# SCHEMATIC.net
KiCad netlist of a schematic drawn in EAGLE
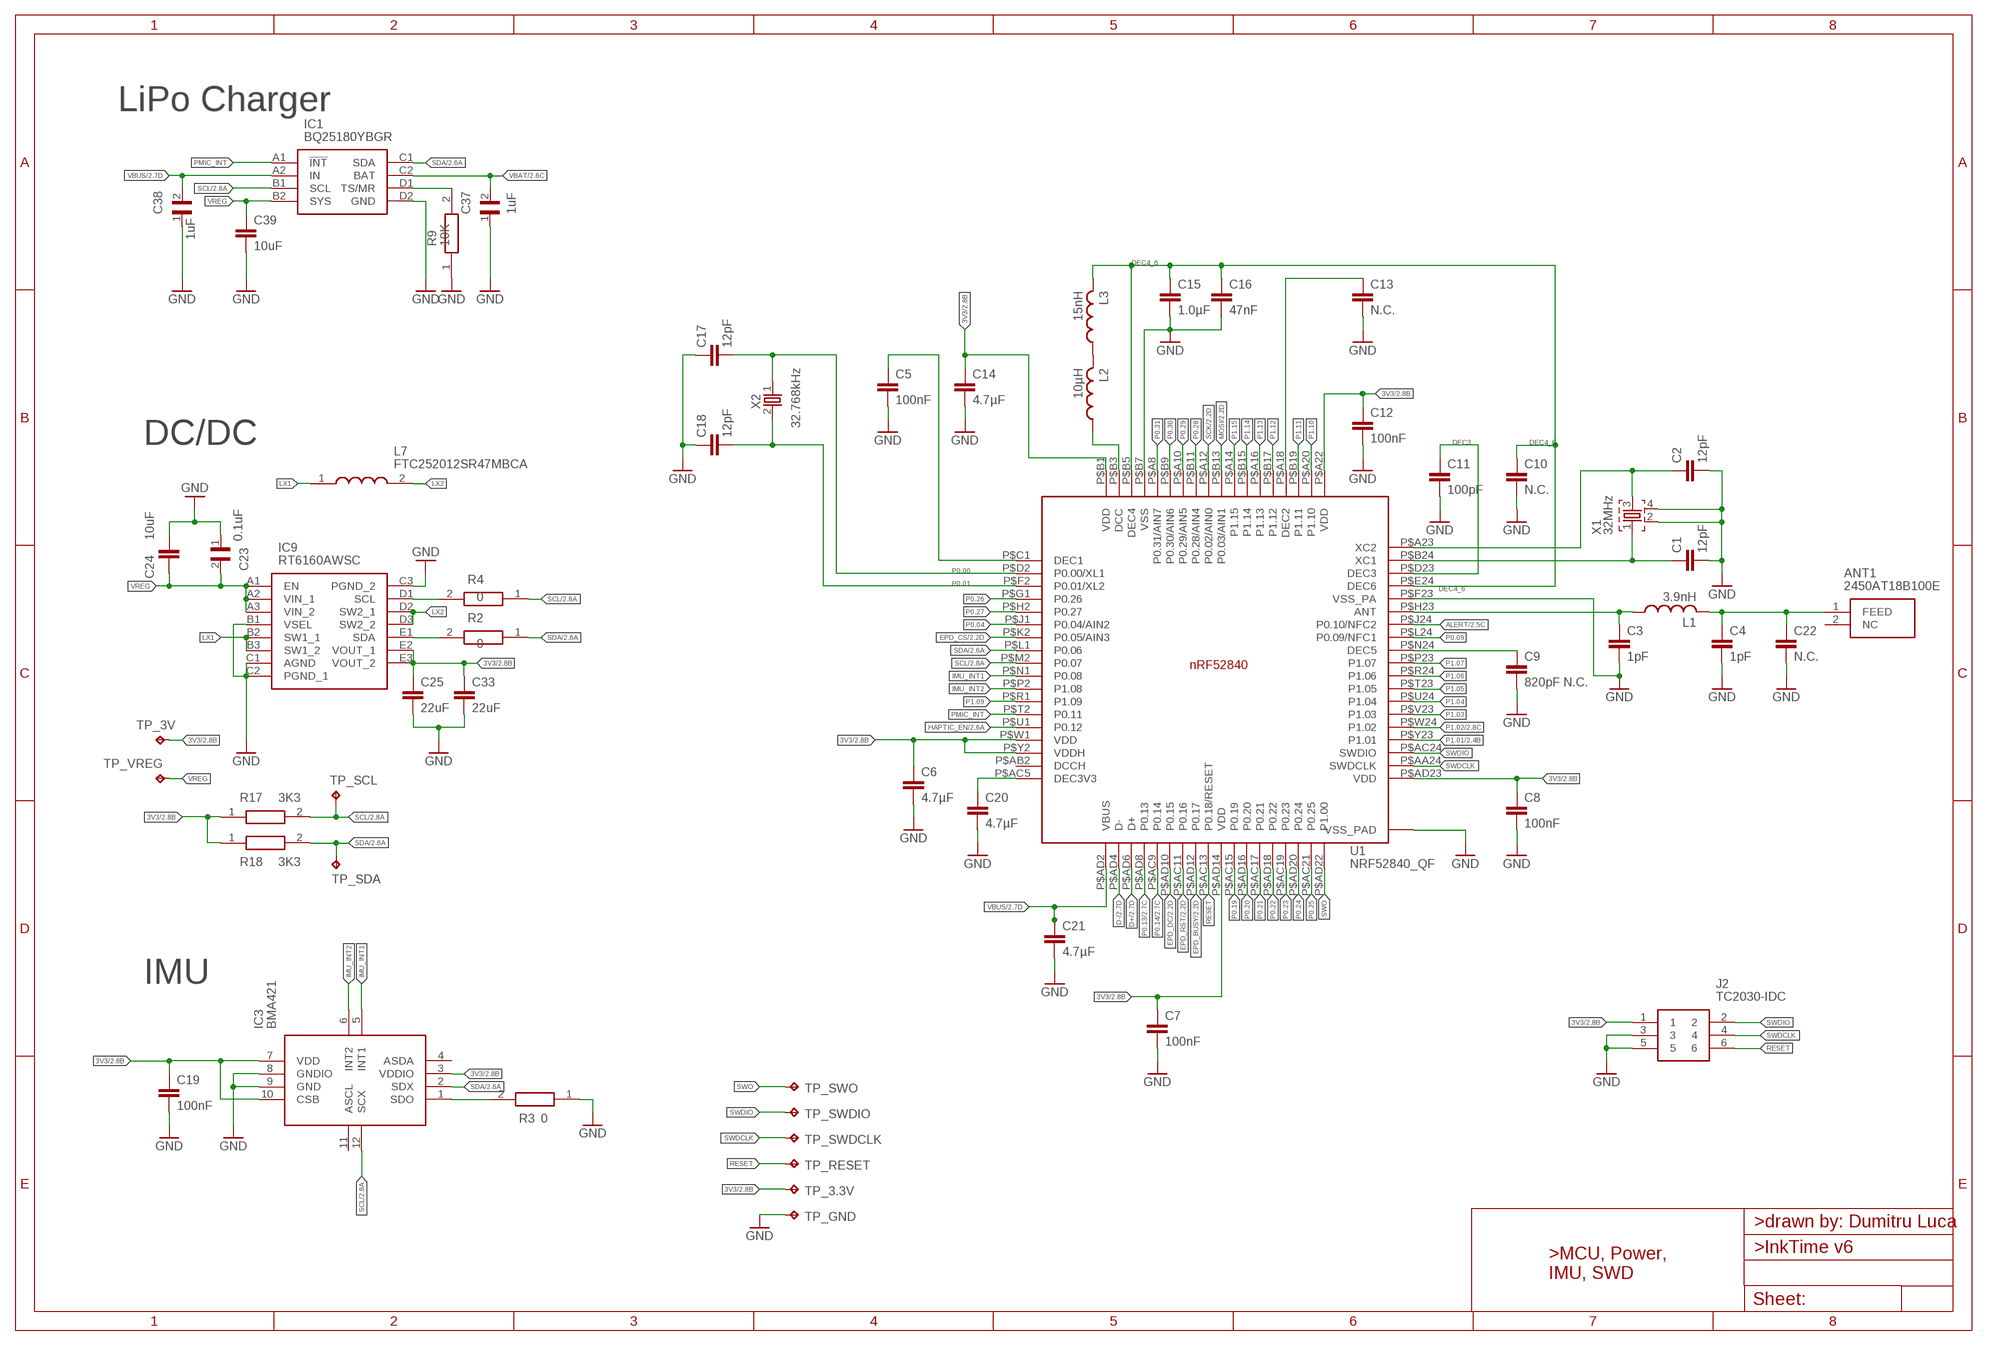
[diagram p0: schematic, sheet 1]
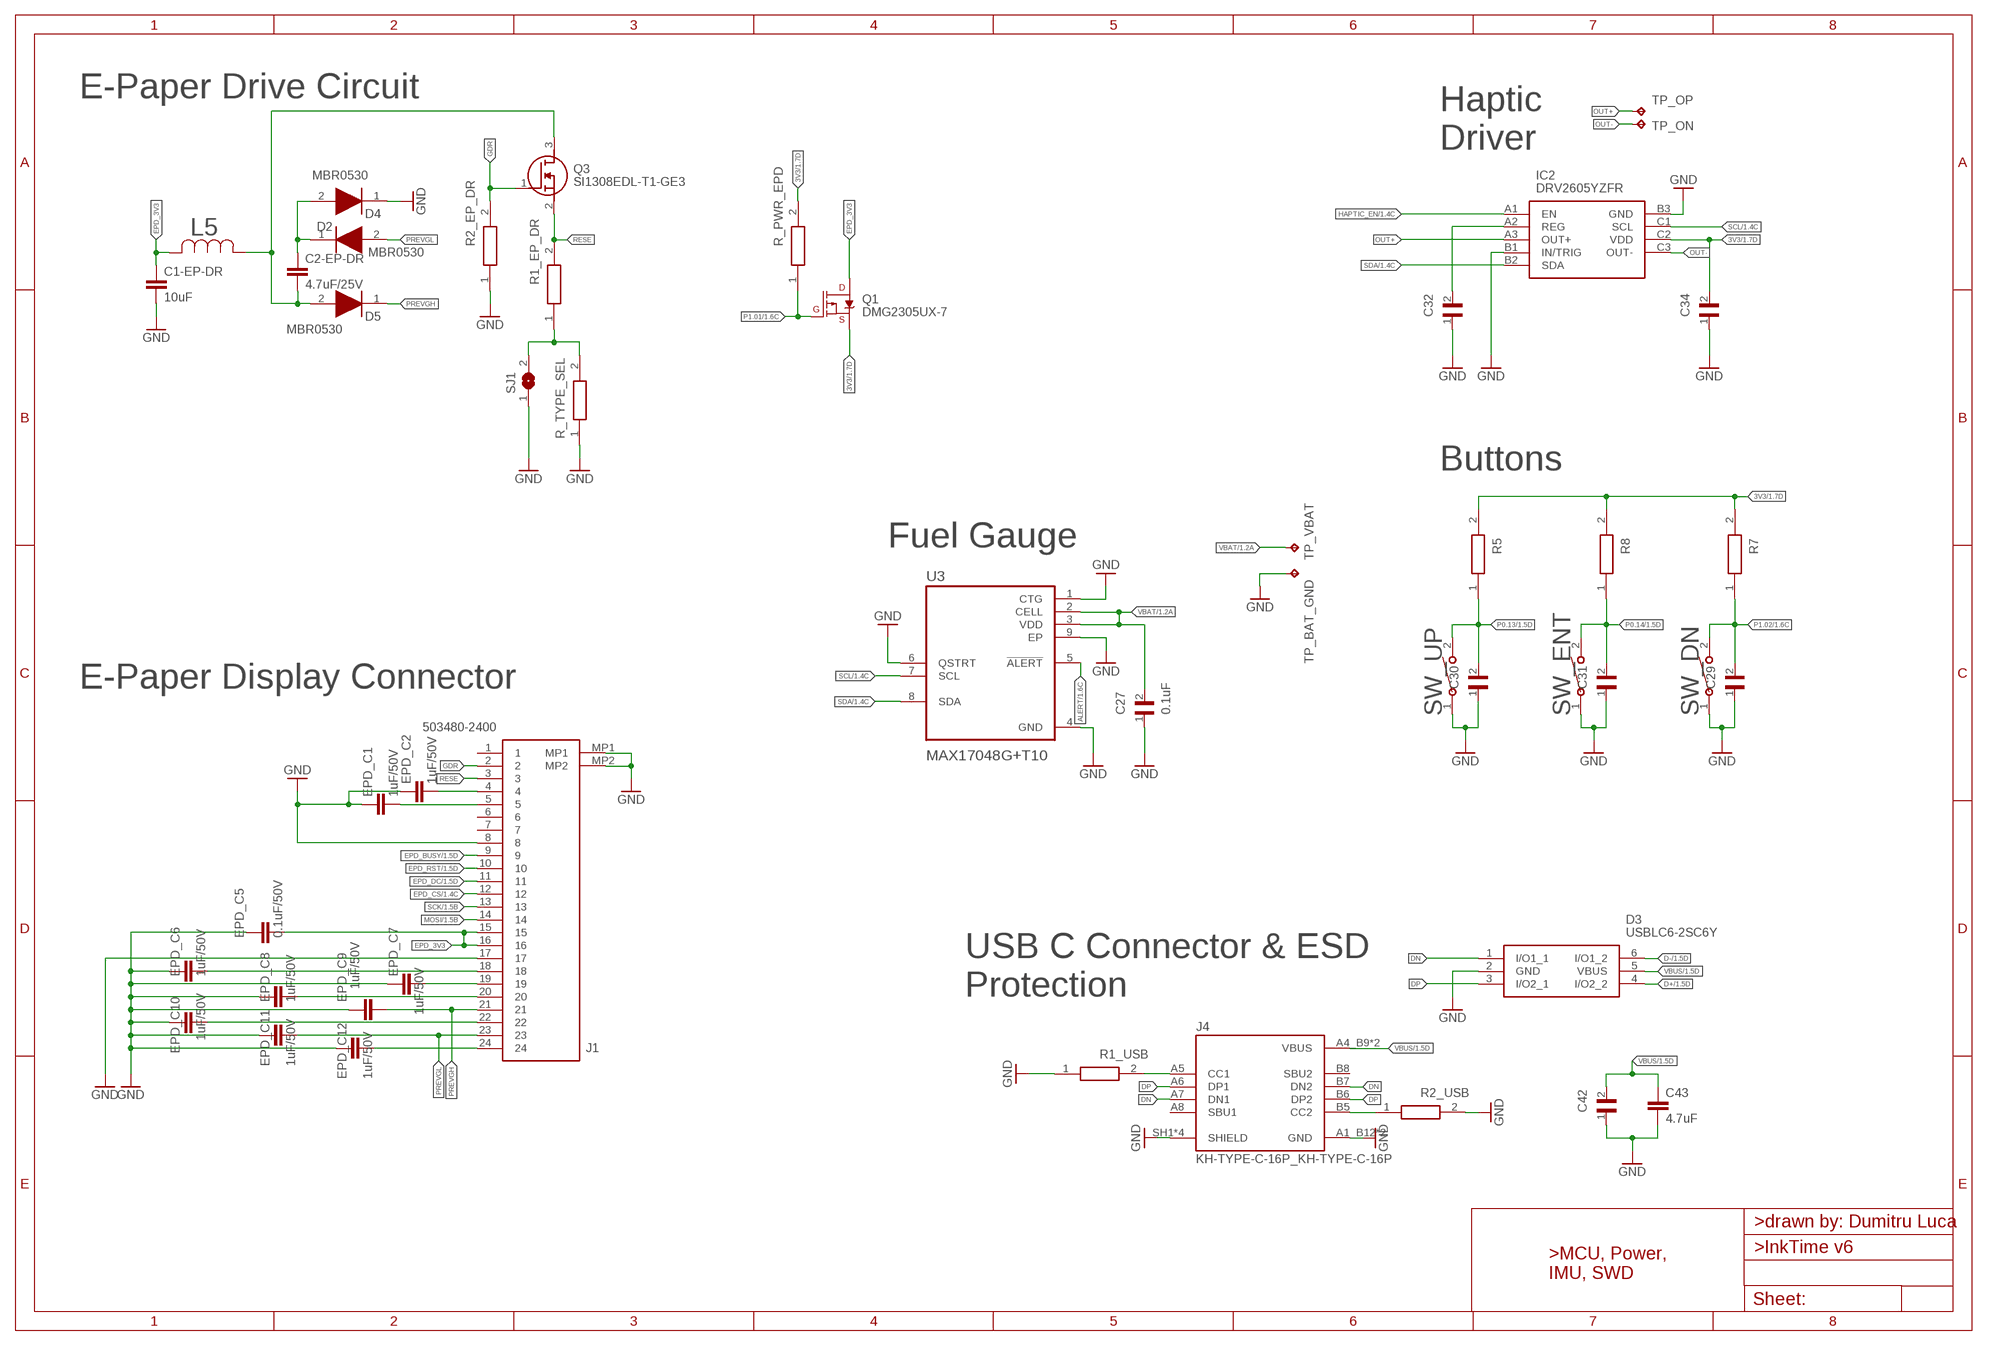
[diagram p1: schematic, sheet 2]

(export (version "E")
  (design (tool "Eeschema 10.0.6"))
  (components
    (comp (ref "ANT1")
      (value "2450AT18B100E")
      (footprint "eagle-import:2450AT18B100E_ANTC3216X140N")
      (fields (field (name "MOUSER_PART_NUMBER") "609-2450AT18B100E"))
      (libsource (lib "eagle-import") (part "2450AT18B100E_2450AT18B100E"))
    )
    (comp (ref "C1")
      (value "12pF")
      (footprint "eagle-import:NORDIC_NRF_3_RESC0201_L")
      (libsource (lib "eagle-import") (part "NORDIC_NRF_3_CAPACITOR_0201_L"))
    )
    (comp (ref "C2")
      (value "12pF")
      (footprint "eagle-import:NORDIC_NRF_3_RESC0201_L")
      (libsource (lib "eagle-import") (part "NORDIC_NRF_3_CAPACITOR_0201_L"))
    )
    (comp (ref "C3")
      (value "1pF")
      (footprint "eagle-import:NORDIC_NRF_3_RESC0201_L")
      (libsource (lib "eagle-import") (part "NORDIC_NRF_3_CAPACITOR_0201_L"))
    )
    (comp (ref "C4")
      (value "1pF")
      (footprint "eagle-import:NORDIC_NRF_3_RESC0201_L")
      (libsource (lib "eagle-import") (part "NORDIC_NRF_3_CAPACITOR_0201_L"))
    )
    (comp (ref "C5")
      (value "100nF")
      (footprint "eagle-import:NORDIC_NRF_3_RESC0201_L")
      (libsource (lib "eagle-import") (part "NORDIC_NRF_3_CAPACITOR_0201_L"))
    )
    (comp (ref "C6")
      (value "4.7µF")
      (footprint "eagle-import:NORDIC_NRF_3_RESC0201_L")
      (libsource (lib "eagle-import") (part "NORDIC_NRF_3_CAPACITOR_0201_L"))
    )
    (comp (ref "C7")
      (value "100nF")
      (footprint "eagle-import:NORDIC_NRF_3_RESC0201_L")
      (libsource (lib "eagle-import") (part "NORDIC_NRF_3_CAPACITOR_0201_L"))
    )
    (comp (ref "C8")
      (value "100nF")
      (footprint "eagle-import:NORDIC_NRF_3_RESC0201_L")
      (libsource (lib "eagle-import") (part "NORDIC_NRF_3_CAPACITOR_0201_L"))
    )
    (comp (ref "C9")
      (value "820pF N.C.")
      (footprint "eagle-import:NORDIC_NRF_3_RESC0201_L")
      (libsource (lib "eagle-import") (part "NORDIC_NRF_3_CAPACITOR_0201_L"))
    )
    (comp (ref "C10")
      (value "N.C.")
      (footprint "eagle-import:NORDIC_NRF_3_RESC0201_L")
      (libsource (lib "eagle-import") (part "NORDIC_NRF_3_CAPACITOR_0201_L"))
    )
    (comp (ref "C11")
      (value "100pF")
      (footprint "eagle-import:NORDIC_NRF_3_RESC0201_L")
      (libsource (lib "eagle-import") (part "NORDIC_NRF_3_CAPACITOR_0201_L"))
    )
    (comp (ref "C12")
      (value "100nF")
      (footprint "eagle-import:NORDIC_NRF_3_RESC0201_L")
      (libsource (lib "eagle-import") (part "NORDIC_NRF_3_CAPACITOR_0201_L"))
    )
    (comp (ref "C13")
      (value "N.C.")
      (footprint "eagle-import:NORDIC_NRF_3_RESC0201_L")
      (libsource (lib "eagle-import") (part "NORDIC_NRF_3_CAPACITOR_0201_L"))
    )
    (comp (ref "C14")
      (value "4.7µF")
      (footprint "eagle-import:NORDIC_NRF_3_RESC0201_L")
      (libsource (lib "eagle-import") (part "NORDIC_NRF_3_CAPACITOR_0201_L"))
    )
    (comp (ref "C15")
      (value "1.0µF")
      (footprint "eagle-import:NORDIC_NRF_3_RESC0201_L")
      (libsource (lib "eagle-import") (part "NORDIC_NRF_3_CAPACITOR_0201_L"))
    )
    (comp (ref "C16")
      (value "47nF")
      (footprint "eagle-import:NORDIC_NRF_3_RESC0201_L")
      (libsource (lib "eagle-import") (part "NORDIC_NRF_3_CAPACITOR_0201_L"))
    )
    (comp (ref "C17")
      (value "12pF")
      (footprint "eagle-import:NORDIC_NRF_3_RESC0201_L")
      (libsource (lib "eagle-import") (part "NORDIC_NRF_3_CAPACITOR_0201_L"))
    )
    (comp (ref "C18")
      (value "12pF")
      (footprint "eagle-import:NORDIC_NRF_3_RESC0201_L")
      (libsource (lib "eagle-import") (part "NORDIC_NRF_3_CAPACITOR_0201_L"))
    )
    (comp (ref "C19")
      (value "100nF")
      (footprint "eagle-import:NORDIC_NRF_3_RESC0201_L")
      (libsource (lib "eagle-import") (part "NORDIC_NRF_3_CAPACITOR_0201_L"))
    )
    (comp (ref "C20")
      (value "4.7µF")
      (footprint "eagle-import:NORDIC_NRF_3_RESC0201_L")
      (libsource (lib "eagle-import") (part "NORDIC_NRF_3_CAPACITOR_0201_L"))
    )
    (comp (ref "C21")
      (value "4.7µF")
      (footprint "eagle-import:NORDIC_NRF_3_RESC0201_L")
      (libsource (lib "eagle-import") (part "NORDIC_NRF_3_CAPACITOR_0201_L"))
    )
    (comp (ref "C22")
      (value "N.C.")
      (footprint "eagle-import:NORDIC_NRF_3_RESC0201_L")
      (libsource (lib "eagle-import") (part "NORDIC_NRF_3_CAPACITOR_0201_L"))
    )
    (comp (ref "C23")
      (value "0.1uF")
      (footprint "eagle-import:GRM011R60J152KE01L_1_0201")
      (libsource (lib "eagle-import") (part "GRM011R60J152KE01L_1_GRM011R60J152KE01L"))
    )
    (comp (ref "C24")
      (value "10uF")
      (footprint "eagle-import:NORDIC_NRF_3_RESC0402_L")
      (libsource (lib "eagle-import") (part "NORDIC_NRF_3_CAPACITOR_0402_L"))
    )
    (comp (ref "C25")
      (value "22uF")
      (footprint "eagle-import:NORDIC_NRF_3_RESC0402_L")
      (libsource (lib "eagle-import") (part "NORDIC_NRF_3_CAPACITOR_0402_L"))
    )
    (comp (ref "C33")
      (value "22uF")
      (footprint "eagle-import:NORDIC_NRF_3_RESC0402_L")
      (libsource (lib "eagle-import") (part "NORDIC_NRF_3_CAPACITOR_0402_L"))
    )
    (comp (ref "C37")
      (value "1uF")
      (footprint "eagle-import:GRM011R60J152KE01L_1_0201")
      (libsource (lib "eagle-import") (part "GRM011R60J152KE01L_1_GRM011R60J152KE01L"))
    )
    (comp (ref "C38")
      (value "1uF")
      (footprint "eagle-import:GRM011R60J152KE01L_1_0201")
      (libsource (lib "eagle-import") (part "GRM011R60J152KE01L_1_GRM011R60J152KE01L"))
    )
    (comp (ref "C39")
      (value "10uF")
      (footprint "eagle-import:NORDIC_NRF_3_RESC0402_L")
      (libsource (lib "eagle-import") (part "NORDIC_NRF_3_CAPACITOR_0402_L"))
    )
    (comp (ref "IC1")
      (value "BQ25180YBGR")
      (footprint "eagle-import:BQ25180YBGR_BGA8C40P2X4_100X155X50")
      (fields (field (name "MOUSER_PART_NUMBER") "595-BQ25180YBGR"))
      (libsource (lib "eagle-import") (part "BQ25180YBGR_BQ25180YBGR"))
    )
    (comp (ref "IC3")
      (value "BMA421")
      (footprint "eagle-import:BMA423_BMA423")
      (fields (field (name "ARROW_PART_NUMBER") "BMA423") (field (name "MOUSER_PART_NUMBER") "262-BMA423"))
      (libsource (lib "eagle-import") (part "BMA423_BMA423"))
    )
    (comp (ref "IC9")
      (value "RT6160AWSC")
      (footprint "eagle-import:RT6160AWSC_BGA15C40P3X5_140X230X60")
      (fields (field (name "MOUSER_PART_NUMBER") "835-RT6160AWSC"))
      (libsource (lib "eagle-import") (part "RT6160AWSC_RT6160AWSC"))
    )
    (comp (ref "J2")
      (value "TC2030-IDC")
      (footprint "eagle-import:TC2030-IDC_TC2030IDC")
      (libsource (lib "eagle-import") (part "TC2030-IDC_TC2030-IDC"))
    )
    (comp (ref "L1")
      (value "3.9nH")
      (footprint "eagle-import:NORDIC_NRF_2_RESC0402_L")
      (libsource (lib "eagle-import") (part "NORDIC_NRF_2_INDUCTOR_0402_L"))
    )
    (comp (ref "L2")
      (value "10µH")
      (footprint "eagle-import:NORDIC_NRF_2_RESC0402_L")
      (libsource (lib "eagle-import") (part "NORDIC_NRF_2_INDUCTOR_0402_L"))
    )
    (comp (ref "L3")
      (value "15nH")
      (footprint "eagle-import:NORDIC_NRF_2_RESC0402_L")
      (libsource (lib "eagle-import") (part "NORDIC_NRF_2_INDUCTOR_0402_L"))
    )
    (comp (ref "L7")
      (value "FTC252012SR47MBCA")
      (footprint "eagle-import:MLP2016SR47MT0S1_INDC2016X100N")
      (libsource (lib "eagle-import") (part "MLP2016SR47MT0S1_FTC252012SR47MBCA"))
    )
    (comp (ref "R2")
      (value "0")
      (footprint "eagle-import:CPF0201D7K68C1_0201")
      (libsource (lib "eagle-import") (part "CPF0201D7K68C1_CPF0201D7K68C1"))
    )
    (comp (ref "R3")
      (value "0")
      (footprint "eagle-import:CPF0201D7K68C1_0201")
      (libsource (lib "eagle-import") (part "CPF0201D7K68C1_CPF0201D7K68C1"))
    )
    (comp (ref "R4")
      (value "0")
      (footprint "eagle-import:CPF0201D7K68C1_0201")
      (libsource (lib "eagle-import") (part "CPF0201D7K68C1_CPF0201D7K68C1"))
    )
    (comp (ref "R9")
      (value "10K")
      (footprint "eagle-import:CPF0201D7K68C1_0201")
      (libsource (lib "eagle-import") (part "CPF0201D7K68C1_CPF0201D7K68C1"))
    )
    (comp (ref "R17")
      (value "3K3")
      (footprint "eagle-import:CPF0201D7K68C1_0201")
      (libsource (lib "eagle-import") (part "CPF0201D7K68C1_CPF0201D7K68C1"))
    )
    (comp (ref "R18")
      (value "3K3")
      (footprint "eagle-import:CPF0201D7K68C1_0201")
      (libsource (lib "eagle-import") (part "CPF0201D7K68C1_CPF0201D7K68C1"))
    )
    (comp (ref "TP_3.3V")
      (value "HECTOR_WATCH_1_TPTP20R")
      (footprint "eagle-import:HECTOR_WATCH_1_TP20R")
      (libsource (lib "eagle-import") (part "HECTOR_WATCH_1_TPTP20R"))
    )
    (comp (ref "TP_3V")
      (value "HECTOR_WATCH_1_TPTP20R")
      (footprint "eagle-import:HECTOR_WATCH_1_TP20R")
      (libsource (lib "eagle-import") (part "HECTOR_WATCH_1_TPTP20R"))
    )
    (comp (ref "TP_GND")
      (value "HECTOR_WATCH_1_TPTP20R")
      (footprint "eagle-import:HECTOR_WATCH_1_TP20R")
      (libsource (lib "eagle-import") (part "HECTOR_WATCH_1_TPTP20R"))
    )
    (comp (ref "TP_RESET")
      (value "HECTOR_WATCH_1_TPTP20R")
      (footprint "eagle-import:HECTOR_WATCH_1_TP20R")
      (libsource (lib "eagle-import") (part "HECTOR_WATCH_1_TPTP20R"))
    )
    (comp (ref "TP_SCL")
      (value "HECTOR_WATCH_1_TPTP20R")
      (footprint "eagle-import:HECTOR_WATCH_1_TP20R")
      (libsource (lib "eagle-import") (part "HECTOR_WATCH_1_TPTP20R"))
    )
    (comp (ref "TP_SDA")
      (value "HECTOR_WATCH_1_TPTP20R")
      (footprint "eagle-import:HECTOR_WATCH_1_TP20R")
      (libsource (lib "eagle-import") (part "HECTOR_WATCH_1_TPTP20R"))
    )
    (comp (ref "TP_SWDCLK")
      (value "HECTOR_WATCH_1_TPTP20R")
      (footprint "eagle-import:HECTOR_WATCH_1_TP20R")
      (libsource (lib "eagle-import") (part "HECTOR_WATCH_1_TPTP20R"))
    )
    (comp (ref "TP_SWDIO")
      (value "HECTOR_WATCH_1_TPTP20R")
      (footprint "eagle-import:HECTOR_WATCH_1_TP20R")
      (libsource (lib "eagle-import") (part "HECTOR_WATCH_1_TPTP20R"))
    )
    (comp (ref "TP_SWO")
      (value "HECTOR_WATCH_1_TPTP20R")
      (footprint "eagle-import:HECTOR_WATCH_1_TP20R")
      (libsource (lib "eagle-import") (part "HECTOR_WATCH_1_TPTP20R"))
    )
    (comp (ref "TP_VREG")
      (value "HECTOR_WATCH_1_TPTP20R")
      (footprint "eagle-import:HECTOR_WATCH_1_TP20R")
      (libsource (lib "eagle-import") (part "HECTOR_WATCH_1_TPTP20R"))
    )
    (comp (ref "U1")
      (value "NRF52840_QF")
      (footprint "eagle-import:NORDIC_NRF_4_AQFN50P700X700X85_HS-74N")
      (libsource (lib "eagle-import") (part "NORDIC_NRF_4_NRF52840_QF"))
    )
    (comp (ref "X1")
      (value "32MHz")
      (footprint "eagle-import:NORDIC_NRF_BT-XTAL_2016_N")
      (libsource (lib "eagle-import") (part "NORDIC_NRF_XTAL_32MHZ"))
    )
    (comp (ref "X2")
      (value "32.768kHz")
      (footprint "eagle-import:NORDIC_NRF_1_XTAL_3215_N")
      (libsource (lib "eagle-import") (part "NORDIC_NRF_1_XTAL_32KHZ"))
    )
    (comp (ref "C1-EP-DR")
      (value "10uF")
      (footprint "eagle-import:NORDIC_NRF_3_RESC0402_L")
      (libsource (lib "eagle-import") (part "NORDIC_NRF_3_CAPACITOR_0402_L"))
    )
    (comp (ref "C2-EP-DR")
      (value "4.7uF/25V")
      (footprint "eagle-import:NORDIC_NRF_3_RESC0201_L")
      (libsource (lib "eagle-import") (part "NORDIC_NRF_3_CAPACITOR_0201_L"))
    )
    (comp (ref "C27")
      (value "0.1uF")
      (footprint "eagle-import:GRM011R60J152KE01L_1_0201")
      (libsource (lib "eagle-import") (part "GRM011R60J152KE01L_1_GRM011R60J152KE01L"))
    )
    (comp (ref "C29")
      (value "1uF")
      (footprint "eagle-import:GRM011R60J152KE01L_1_0201")
      (libsource (lib "eagle-import") (part "GRM011R60J152KE01L_1_GRM011R60J152KE01L"))
    )
    (comp (ref "C30")
      (value "1uF")
      (footprint "eagle-import:GRM011R60J152KE01L_1_0201")
      (libsource (lib "eagle-import") (part "GRM011R60J152KE01L_1_GRM011R60J152KE01L"))
    )
    (comp (ref "C31")
      (value "1uF")
      (footprint "eagle-import:GRM011R60J152KE01L_1_0201")
      (libsource (lib "eagle-import") (part "GRM011R60J152KE01L_1_GRM011R60J152KE01L"))
    )
    (comp (ref "C32")
      (value "1uF")
      (footprint "eagle-import:GRM011R60J152KE01L_1_0201")
      (libsource (lib "eagle-import") (part "GRM011R60J152KE01L_1_GRM011R60J152KE01L"))
    )
    (comp (ref "C34")
      (value "0.1uF")
      (footprint "eagle-import:GRM011R60J152KE01L_1_0201")
      (libsource (lib "eagle-import") (part "GRM011R60J152KE01L_1_GRM011R60J152KE01L"))
    )
    (comp (ref "C42")
      (value "0.1uF")
      (footprint "eagle-import:GRM011R60J152KE01L_1_0201")
      (libsource (lib "eagle-import") (part "GRM011R60J152KE01L_1_GRM011R60J152KE01L"))
    )
    (comp (ref "C43")
      (value "4.7uF")
      (footprint "eagle-import:NORDIC_NRF_3_RESC0201_L")
      (libsource (lib "eagle-import") (part "NORDIC_NRF_3_CAPACITOR_0201_L"))
    )
    (comp (ref "D2")
      (value "MBR0530")
      (footprint "eagle-import:ESP32_C6_LIBRARY_5_SOD3716X135N")
      (fields (field (name "MF") "ON Semiconductor"))
      (libsource (lib "eagle-import") (part "ESP32_C6_LIBRARY_5_MBR0530"))
    )
    (comp (ref "D3")
      (value "USBLC6-2SC6Y")
      (footprint "eagle-import:ESP32_C6_LIBRARY_3_SOT95P280X145-6N")
      (fields (field (name "MF") "STMicroelectronics"))
      (libsource (lib "eagle-import") (part "ESP32_C6_LIBRARY_3_USBLC6-2SC6Y"))
    )
    (comp (ref "D4")
      (value "MBR0530")
      (footprint "eagle-import:ESP32_C6_LIBRARY_5_SOD3716X135N")
      (fields (field (name "MF") "ON Semiconductor"))
      (libsource (lib "eagle-import") (part "ESP32_C6_LIBRARY_5_MBR0530"))
    )
    (comp (ref "D5")
      (value "MBR0530")
      (footprint "eagle-import:ESP32_C6_LIBRARY_5_SOD3716X135N")
      (fields (field (name "MF") "ON Semiconductor"))
      (libsource (lib "eagle-import") (part "ESP32_C6_LIBRARY_5_MBR0530"))
    )
    (comp (ref "EPD_C1")
      (value "1uF/50V")
      (footprint "eagle-import:NORDIC_NRF_3_RESC0201_L")
      (libsource (lib "eagle-import") (part "NORDIC_NRF_3_CAPACITOR_0201_L"))
    )
    (comp (ref "EPD_C2")
      (value "1uF/50V")
      (footprint "eagle-import:NORDIC_NRF_3_RESC0201_L")
      (libsource (lib "eagle-import") (part "NORDIC_NRF_3_CAPACITOR_0201_L"))
    )
    (comp (ref "EPD_C5")
      (value "0.1uF/50V")
      (footprint "eagle-import:NORDIC_NRF_3_RESC0201_L")
      (libsource (lib "eagle-import") (part "NORDIC_NRF_3_CAPACITOR_0201_L"))
    )
    (comp (ref "EPD_C6")
      (value "1uF/50V")
      (footprint "eagle-import:NORDIC_NRF_3_RESC0201_L")
      (libsource (lib "eagle-import") (part "NORDIC_NRF_3_CAPACITOR_0201_L"))
    )
    (comp (ref "EPD_C7")
      (value "1uF/50V")
      (footprint "eagle-import:NORDIC_NRF_3_RESC0201_L")
      (libsource (lib "eagle-import") (part "NORDIC_NRF_3_CAPACITOR_0201_L"))
    )
    (comp (ref "EPD_C8")
      (value "1uF/50V")
      (footprint "eagle-import:NORDIC_NRF_3_RESC0201_L")
      (libsource (lib "eagle-import") (part "NORDIC_NRF_3_CAPACITOR_0201_L"))
    )
    (comp (ref "EPD_C9")
      (value "1uF/50V")
      (footprint "eagle-import:NORDIC_NRF_3_RESC0201_L")
      (libsource (lib "eagle-import") (part "NORDIC_NRF_3_CAPACITOR_0201_L"))
    )
    (comp (ref "EPD_C10")
      (value "1uF/50V")
      (footprint "eagle-import:NORDIC_NRF_3_RESC0201_L")
      (libsource (lib "eagle-import") (part "NORDIC_NRF_3_CAPACITOR_0201_L"))
    )
    (comp (ref "EPD_C11")
      (value "1uF/50V")
      (footprint "eagle-import:NORDIC_NRF_3_RESC0201_L")
      (libsource (lib "eagle-import") (part "NORDIC_NRF_3_CAPACITOR_0201_L"))
    )
    (comp (ref "EPD_C12")
      (value "1uF/50V")
      (footprint "eagle-import:NORDIC_NRF_3_RESC0201_L")
      (libsource (lib "eagle-import") (part "NORDIC_NRF_3_CAPACITOR_0201_L"))
    )
    (comp (ref "IC2")
      (value "DRV2605YZFR")
      (footprint "eagle-import:DRV2605YZFR_BGA9C50P3X3_144X144X62")
      (libsource (lib "eagle-import") (part "DRV2605YZFR_DRV2605YZFR"))
    )
    (comp (ref "J1")
      (value "503480-2400")
      (footprint "eagle-import:503480-2400_5034802400")
      (fields (field (name "MOUSER_PART_NUMBER") "538-503480-2400"))
      (libsource (lib "eagle-import") (part "503480-2400_503480-2400"))
    )
    (comp (ref "J4")
      (value "KH-TYPE-C-16P_KH-TYPE-C-16P")
      (footprint "eagle-import:KH-TYPE-C-16P_KINGHELM_KH-TYPE-C-16P")
      (fields (field (name "MF") "kinghelm") (field (name "MP") "KH-TYPE-C-16P"))
      (libsource (lib "eagle-import") (part "KH-TYPE-C-16P_KH-TYPE-C-16P"))
    )
    (comp (ref "L5")
      (value "ESP32_C6_LIBRARY_2_744043680IND_4828-WE-TPC_WRE")
      (footprint "eagle-import:ESP32_C6_LIBRARY_2_IND_4828-WE-TPC_WRE")
      (fields
        (field (name "MANUFACTURER_PART_NUMBER") "744043680")
        (field (name "COPYRIGHT") "Copyright (C) 2024 Ultra Librarian. All rights reserved.")
      )
      (libsource (lib "eagle-import") (part "ESP32_C6_LIBRARY_2_744043680IND_4828-WE-TPC_WRE"))
    )
    (comp (ref "Q1")
      (value "DMG2305UX-7")
      (footprint "eagle-import:ESP32_C6_LIBRARY_4_ESP32_C6_LIBRARY_4_ESP32_C6_LIBRARY_4_ESP32_C6_LIBRARY_4_ESP32_WROVER_SPARKFUN-DISCRETESEMI_SOT23-3")
      (libsource (lib "eagle-import") (part "ESP32_C6_LIBRARY_4_ESP32_WROVER_SPARKFUN-DISCRETESEMI_MOSFET_PCH-DMG2305UX-7"))
    )
    (comp (ref "Q3")
      (value "SI1308EDL-T1-GE3")
      (footprint "eagle-import:ESP32_C6_LIBRARY_6_SOT65P210X110-3N")
      (fields (field (name "MF") "Vishay Siliconix"))
      (libsource (lib "eagle-import") (part "ESP32_C6_LIBRARY_6_SI1308EDL-T1-GE3"))
    )
    (comp (ref "R1_EP_DR")
      (value "0.47")
      (footprint "eagle-import:CPF0201D7K68C1_0201")
      (libsource (lib "eagle-import") (part "CPF0201D7K68C1_CPF0201D7K68C1"))
    )
    (comp (ref "R1_USB")
      (value "5K1")
      (footprint "eagle-import:CPF0201D7K68C1_0201")
      (libsource (lib "eagle-import") (part "CPF0201D7K68C1_CPF0201D7K68C1"))
    )
    (comp (ref "R2_EP_DR")
      (value "10K")
      (footprint "eagle-import:CPF0201D7K68C1_0201")
      (libsource (lib "eagle-import") (part "CPF0201D7K68C1_CPF0201D7K68C1"))
    )
    (comp (ref "R2_USB")
      (value "5K1")
      (footprint "eagle-import:CPF0201D7K68C1_0201")
      (libsource (lib "eagle-import") (part "CPF0201D7K68C1_CPF0201D7K68C1"))
    )
    (comp (ref "R5")
      (value "10K")
      (footprint "eagle-import:CPF0201D7K68C1_0201")
      (libsource (lib "eagle-import") (part "CPF0201D7K68C1_CPF0201D7K68C1"))
    )
    (comp (ref "R7")
      (value "10K")
      (footprint "eagle-import:CPF0201D7K68C1_0201")
      (libsource (lib "eagle-import") (part "CPF0201D7K68C1_CPF0201D7K68C1"))
    )
    (comp (ref "R8")
      (value "10K")
      (footprint "eagle-import:CPF0201D7K68C1_0201")
      (libsource (lib "eagle-import") (part "CPF0201D7K68C1_CPF0201D7K68C1"))
    )
    (comp (ref "R_PWR_EPD")
      (value "10K")
      (footprint "eagle-import:CPF0201D7K68C1_0201")
      (libsource (lib "eagle-import") (part "CPF0201D7K68C1_CPF0201D7K68C1"))
    )
    (comp (ref "R_TYPE_SEL")
      (value "2.2")
      (footprint "eagle-import:CPF0201D7K68C1_0201")
      (libsource (lib "eagle-import") (part "CPF0201D7K68C1_CPF0201D7K68C1"))
    )
    (comp (ref "SJ1")
      (value "ESP32_C6_LIBRARY_7_JUMPER_SJ")
      (footprint "eagle-import:ESP32_C6_LIBRARY_7_JUMPER_SJ")
      (libsource (lib "eagle-import") (part "ESP32_C6_LIBRARY_7_JUMPER_SJ"))
    )
    (comp (ref "SW_DN")
      (value "2025-10-22_07-23-44_LIBRARY_EVP-AKE31ASW_EVP-AKE31A_PAN")
      (footprint "eagle-import:2025-10-22_07-23-44_LIBRARY_SW_EVP-AKE31A_PAN")
      (fields
        (field (name "MANUFACTURER_PART_NUMBER") "EVP-AKE31A")
        (field (name "COPYRIGHT") "Copyright (C) 2025 Ultra Librarian. All rights reserved.")
      )
      (libsource (lib "eagle-import") (part "2025-10-22_07-23-44_LIBRARY_EVP-AKE31ASW_EVP-AKE31A_PAN"))
    )
    (comp (ref "SW_ENT")
      (value "2025-10-22_07-23-44_LIBRARY_EVP-AKE31ASW_EVP-AKE31A_PAN")
      (footprint "eagle-import:2025-10-22_07-23-44_LIBRARY_SW_EVP-AKE31A_PAN")
      (fields
        (field (name "MANUFACTURER_PART_NUMBER") "EVP-AKE31A")
        (field (name "COPYRIGHT") "Copyright (C) 2025 Ultra Librarian. All rights reserved.")
      )
      (libsource (lib "eagle-import") (part "2025-10-22_07-23-44_LIBRARY_EVP-AKE31ASW_EVP-AKE31A_PAN"))
    )
    (comp (ref "SW_UP")
      (value "2025-10-22_07-23-44_LIBRARY_EVP-AKE31ASW_EVP-AKE31A_PAN")
      (footprint "eagle-import:2025-10-22_07-23-44_LIBRARY_SW_EVP-AKE31A_PAN")
      (fields
        (field (name "MANUFACTURER_PART_NUMBER") "EVP-AKE31A")
        (field (name "COPYRIGHT") "Copyright (C) 2025 Ultra Librarian. All rights reserved.")
      )
      (libsource (lib "eagle-import") (part "2025-10-22_07-23-44_LIBRARY_EVP-AKE31ASW_EVP-AKE31A_PAN"))
    )
    (comp (ref "TP_BAT_GND")
      (value "HECTOR_WATCH_1_TPTP20R")
      (footprint "eagle-import:HECTOR_WATCH_1_TP20R")
      (libsource (lib "eagle-import") (part "HECTOR_WATCH_1_TPTP20R"))
    )
    (comp (ref "TP_ON")
      (value "HECTOR_WATCH_1_TPTP20R")
      (footprint "eagle-import:HECTOR_WATCH_1_TP20R")
      (libsource (lib "eagle-import") (part "HECTOR_WATCH_1_TPTP20R"))
    )
    (comp (ref "TP_OP")
      (value "HECTOR_WATCH_1_TPTP20R")
      (footprint "eagle-import:HECTOR_WATCH_1_TP20R")
      (libsource (lib "eagle-import") (part "HECTOR_WATCH_1_TPTP20R"))
    )
    (comp (ref "TP_VBAT")
      (value "HECTOR_WATCH_1_TPTP20R")
      (footprint "eagle-import:HECTOR_WATCH_1_TP20R")
      (libsource (lib "eagle-import") (part "HECTOR_WATCH_1_TPTP20R"))
    )
    (comp (ref "U3")
      (value "MAX17048G+T10")
      (footprint "eagle-import:ESP32_C6_LIBRARY_SON50P200X200X80-9N")
      (fields (field (name "MF") "Analog Devices"))
      (libsource (lib "eagle-import") (part "ESP32_C6_LIBRARY_MAX17048G+T10"))
    )
  )
  (nets
    (net (code "1") (name "3V3") (class "Default")
      (node (ref "C12") (pin "1") (pinfunction "1_1") (pintype "passive"))
      (node (ref "C14") (pin "1") (pinfunction "1_1") (pintype "passive"))
      (node (ref "C19") (pin "1") (pinfunction "1_1") (pintype "passive"))
      (node (ref "C25") (pin "1") (pinfunction "1_1") (pintype "passive"))
      (node (ref "C33") (pin "1") (pinfunction "1_1") (pintype "passive"))
      (node (ref "C34") (pin "2") (pinfunction "2_2") (pintype "passive"))
      (node (ref "C6") (pin "1") (pinfunction "1_1") (pintype "passive"))
      (node (ref "C7") (pin "1") (pinfunction "1_1") (pintype "passive"))
      (node (ref "C8") (pin "1") (pinfunction "1_1") (pintype "passive"))
      (node (ref "IC2") (pin "C2") (pinfunction "VDD_C2") (pintype "bidirectional"))
      (node (ref "IC3") (pin "10") (pinfunction "CSB_10") (pintype "bidirectional"))
      (node (ref "IC3") (pin "3") (pinfunction "VDDIO_3") (pintype "bidirectional"))
      (node (ref "IC3") (pin "7") (pinfunction "VDD_7") (pintype "bidirectional"))
      (node (ref "IC9") (pin "E2") (pinfunction "VOUT_1_E2") (pintype "bidirectional"))
      (node (ref "IC9") (pin "E3") (pinfunction "VOUT_2_E3") (pintype "bidirectional"))
      (node (ref "J2") (pin "1") (pinfunction "1_1") (pintype "bidirectional"))
      (node (ref "Q1") (pin "2") (pinfunction "S_2") (pintype "bidirectional"))
      (node (ref "R17") (pin "1") (pinfunction "1_1") (pintype "bidirectional"))
      (node (ref "R18") (pin "1") (pinfunction "1_1") (pintype "bidirectional"))
      (node (ref "R5") (pin "2") (pinfunction "2_2") (pintype "bidirectional"))
      (node (ref "R7") (pin "2") (pinfunction "2_2") (pintype "bidirectional"))
      (node (ref "R8") (pin "2") (pinfunction "2_2") (pintype "bidirectional"))
      (node (ref "R_PWR_EPD") (pin "2") (pinfunction "2_2") (pintype "bidirectional"))
      (node (ref "TP_3.3V") (pin "TP") (pinfunction "TP_TP") (pintype "input"))
      (node (ref "TP_3V") (pin "TP") (pinfunction "TP_TP") (pintype "input"))
      (node (ref "U1") (pin "P$A22") (pinfunction "VDD_P$A22") (pintype "power_in"))
      (node (ref "U1") (pin "P$AD14") (pinfunction "VDD_P$AD14") (pintype "power_in"))
      (node (ref "U1") (pin "P$AD23") (pinfunction "VDD_P$AD23") (pintype "power_in"))
      (node (ref "U1") (pin "P$B1") (pinfunction "VDD_P$B1") (pintype "power_in"))
      (node (ref "U1") (pin "P$W1") (pinfunction "VDD_P$W1") (pintype "power_in"))
      (node (ref "U1") (pin "P$Y2") (pinfunction "VDDH_P$Y2") (pintype "power_in"))
    )
    (net (code "2") (name "ALERT") (class "Default")
      (node (ref "U1") (pin "P$J24") (pinfunction "P0.10/NFC2_P$J24") (pintype "bidirectional"))
      (node (ref "U3") (pin "5") (pinfunction "~{ALERT}_5") (pintype "output"))
    )
    (net (code "3") (name "D+") (class "Default")
      (node (ref "D3") (pin "4") (pinfunction "I/O2_2_4") (pintype "bidirectional"))
      (node (ref "U1") (pin "P$AD6") (pinfunction "D+_P$AD6") (pintype "bidirectional"))
    )
    (net (code "4") (name "D-") (class "Default")
      (node (ref "D3") (pin "6") (pinfunction "I/O1_2_6") (pintype "bidirectional"))
      (node (ref "U1") (pin "P$AD4") (pinfunction "D-_P$AD4") (pintype "bidirectional"))
    )
    (net (code "5") (name "DEC3") (class "Default")
      (node (ref "C11") (pin "1") (pinfunction "1_1") (pintype "passive"))
      (node (ref "U1") (pin "P$D23") (pinfunction "DEC3_P$D23") (pintype "bidirectional"))
    )
    (net (code "6") (name "DEC4_6") (class "Default")
      (node (ref "C10") (pin "1") (pinfunction "1_1") (pintype "passive"))
      (node (ref "C15") (pin "1") (pinfunction "1_1") (pintype "passive"))
      (node (ref "C16") (pin "1") (pinfunction "1_1") (pintype "passive"))
      (node (ref "L3") (pin "2") (pinfunction "2_2") (pintype "passive"))
      (node (ref "U1") (pin "P$B5") (pinfunction "DEC4_P$B5") (pintype "power_in"))
      (node (ref "U1") (pin "P$E24") (pinfunction "DEC6_P$E24") (pintype "bidirectional"))
    )
    (net (code "7") (name "DN") (class "Default")
      (node (ref "D3") (pin "1") (pinfunction "I/O1_1_1") (pintype "bidirectional"))
      (node (ref "J4") (pin "A7") (pinfunction "DN1_A7") (pintype "bidirectional"))
      (node (ref "J4") (pin "B7") (pinfunction "DN2_B7") (pintype "bidirectional"))
    )
    (net (code "8") (name "DP") (class "Default")
      (node (ref "D3") (pin "3") (pinfunction "I/O2_1_3") (pintype "bidirectional"))
      (node (ref "J4") (pin "A6") (pinfunction "DP1_A6") (pintype "bidirectional"))
      (node (ref "J4") (pin "B6") (pinfunction "DP2_B6") (pintype "bidirectional"))
    )
    (net (code "9") (name "EPD_3V3") (class "Default")
      (node (ref "C1-EP-DR") (pin "1") (pinfunction "1_1") (pintype "passive"))
      (node (ref "EPD_C5") (pin "2") (pinfunction "2_2") (pintype "passive"))
      (node (ref "J1") (pin "15") (pinfunction "15_15") (pintype "bidirectional"))
      (node (ref "J1") (pin "16") (pinfunction "16_16") (pintype "bidirectional"))
      (node (ref "L5") (pin "2") (pinfunction "2_2") (pintype "passive"))
      (node (ref "Q1") (pin "3") (pinfunction "D_3") (pintype "bidirectional"))
    )
    (net (code "10") (name "EPD_BUSY") (class "Default")
      (node (ref "J1") (pin "9") (pinfunction "9_9") (pintype "bidirectional"))
      (node (ref "U1") (pin "P$AD12") (pinfunction "P0.17_P$AD12") (pintype "bidirectional"))
    )
    (net (code "11") (name "EPD_CS") (class "Default")
      (node (ref "J1") (pin "12") (pinfunction "12_12") (pintype "bidirectional"))
      (node (ref "U1") (pin "P$K2") (pinfunction "P0.05/AIN3_P$K2") (pintype "bidirectional"))
    )
    (net (code "12") (name "EPD_DC") (class "Default")
      (node (ref "J1") (pin "11") (pinfunction "11_11") (pintype "bidirectional"))
      (node (ref "U1") (pin "P$AD10") (pinfunction "P0.15_P$AD10") (pintype "bidirectional"))
    )
    (net (code "13") (name "EPD_RST") (class "Default")
      (node (ref "J1") (pin "10") (pinfunction "10_10") (pintype "bidirectional"))
      (node (ref "U1") (pin "P$AC11") (pinfunction "P0.16_P$AC11") (pintype "bidirectional"))
    )
    (net (code "14") (name "GDR") (class "Default")
      (node (ref "J1") (pin "2") (pinfunction "2_2") (pintype "bidirectional"))
      (node (ref "Q3") (pin "1") (pinfunction "G_1") (pintype "bidirectional"))
      (node (ref "R2_EP_DR") (pin "2") (pinfunction "2_2") (pintype "bidirectional"))
    )
    (net (code "15") (name "GND") (class "Default")
      (node (ref "C1") (pin "2") (pinfunction "2_2") (pintype "passive"))
      (node (ref "C1-EP-DR") (pin "2") (pinfunction "2_2") (pintype "passive"))
      (node (ref "C10") (pin "2") (pinfunction "2_2") (pintype "passive"))
      (node (ref "C11") (pin "2") (pinfunction "2_2") (pintype "passive"))
      (node (ref "C12") (pin "2") (pinfunction "2_2") (pintype "passive"))
      (node (ref "C13") (pin "2") (pinfunction "2_2") (pintype "passive"))
      (node (ref "C14") (pin "2") (pinfunction "2_2") (pintype "passive"))
      (node (ref "C15") (pin "2") (pinfunction "2_2") (pintype "passive"))
      (node (ref "C16") (pin "2") (pinfunction "2_2") (pintype "passive"))
      (node (ref "C17") (pin "1") (pinfunction "1_1") (pintype "passive"))
      (node (ref "C18") (pin "1") (pinfunction "1_1") (pintype "passive"))
      (node (ref "C19") (pin "2") (pinfunction "2_2") (pintype "passive"))
      (node (ref "C2") (pin "2") (pinfunction "2_2") (pintype "passive"))
      (node (ref "C20") (pin "2") (pinfunction "2_2") (pintype "passive"))
      (node (ref "C21") (pin "2") (pinfunction "2_2") (pintype "passive"))
      (node (ref "C22") (pin "2") (pinfunction "2_2") (pintype "passive"))
      (node (ref "C23") (pin "1") (pinfunction "1_1") (pintype "passive"))
      (node (ref "C24") (pin "1") (pinfunction "1_1") (pintype "passive"))
      (node (ref "C25") (pin "2") (pinfunction "2_2") (pintype "passive"))
      (node (ref "C27") (pin "1") (pinfunction "1_1") (pintype "passive"))
      (node (ref "C29") (pin "1") (pinfunction "1_1") (pintype "passive"))
      (node (ref "C3") (pin "2") (pinfunction "2_2") (pintype "passive"))
      (node (ref "C30") (pin "1") (pinfunction "1_1") (pintype "passive"))
      (node (ref "C31") (pin "1") (pinfunction "1_1") (pintype "passive"))
      (node (ref "C32") (pin "1") (pinfunction "1_1") (pintype "passive"))
      (node (ref "C33") (pin "2") (pinfunction "2_2") (pintype "passive"))
      (node (ref "C34") (pin "1") (pinfunction "1_1") (pintype "passive"))
      (node (ref "C37") (pin "1") (pinfunction "1_1") (pintype "passive"))
      (node (ref "C38") (pin "1") (pinfunction "1_1") (pintype "passive"))
      (node (ref "C39") (pin "2") (pinfunction "2_2") (pintype "passive"))
      (node (ref "C4") (pin "2") (pinfunction "2_2") (pintype "passive"))
      (node (ref "C42") (pin "1") (pinfunction "1_1") (pintype "passive"))
      (node (ref "C43") (pin "2") (pinfunction "2_2") (pintype "passive"))
      (node (ref "C5") (pin "2") (pinfunction "2_2") (pintype "passive"))
      (node (ref "C6") (pin "2") (pinfunction "2_2") (pintype "passive"))
      (node (ref "C7") (pin "2") (pinfunction "2_2") (pintype "passive"))
      (node (ref "C8") (pin "2") (pinfunction "2_2") (pintype "passive"))
      (node (ref "C9") (pin "2") (pinfunction "2_2") (pintype "passive"))
      (node (ref "D3") (pin "2") (pinfunction "GND_2") (pintype "bidirectional"))
      (node (ref "D4") (pin "1") (pinfunction "K_1") (pintype "bidirectional"))
      (node (ref "EPD_C1") (pin "1") (pinfunction "1_1") (pintype "passive"))
      (node (ref "EPD_C10") (pin "1") (pinfunction "1_1") (pintype "passive"))
      (node (ref "EPD_C11") (pin "1") (pinfunction "1_1") (pintype "passive"))
      (node (ref "EPD_C12") (pin "1") (pinfunction "1_1") (pintype "passive"))
      (node (ref "EPD_C2") (pin "1") (pinfunction "1_1") (pintype "passive"))
      (node (ref "EPD_C5") (pin "1") (pinfunction "1_1") (pintype "passive"))
      (node (ref "EPD_C6") (pin "1") (pinfunction "1_1") (pintype "passive"))
      (node (ref "EPD_C7") (pin "1") (pinfunction "1_1") (pintype "passive"))
      (node (ref "EPD_C8") (pin "1") (pinfunction "1_1") (pintype "passive"))
      (node (ref "EPD_C9") (pin "1") (pinfunction "1_1") (pintype "passive"))
      (node (ref "IC1") (pin "D2") (pinfunction "GND_D2") (pintype "bidirectional"))
      (node (ref "IC2") (pin "B1") (pinfunction "IN/TRIG_B1") (pintype "bidirectional"))
      (node (ref "IC2") (pin "B3") (pinfunction "GND_B3") (pintype "bidirectional"))
      (node (ref "IC3") (pin "8") (pinfunction "GNDIO_8") (pintype "bidirectional"))
      (node (ref "IC3") (pin "9") (pinfunction "GND_9") (pintype "bidirectional"))
      (node (ref "IC9") (pin "B1") (pinfunction "VSEL_B1") (pintype "bidirectional"))
      (node (ref "IC9") (pin "C1") (pinfunction "AGND_C1") (pintype "bidirectional"))
      (node (ref "IC9") (pin "C2") (pinfunction "PGND_1_C2") (pintype "bidirectional"))
      (node (ref "IC9") (pin "C3") (pinfunction "PGND_2_C3") (pintype "bidirectional"))
      (node (ref "J1") (pin "17") (pinfunction "17_17") (pintype "bidirectional"))
      (node (ref "J1") (pin "8") (pinfunction "8_8") (pintype "bidirectional"))
      (node (ref "J1") (pin "MP1") (pinfunction "MP1_MP1") (pintype "bidirectional"))
      (node (ref "J1") (pin "MP2") (pinfunction "MP2_MP2") (pintype "bidirectional"))
      (node (ref "J2") (pin "3") (pinfunction "3_3") (pintype "bidirectional"))
      (node (ref "J2") (pin "5") (pinfunction "5_5") (pintype "bidirectional"))
      (node (ref "J4") (pin "A12_B1") (pinfunction "GND_A12_B1") (pintype "power_in"))
      (node (ref "J4") (pin "A1_B12") (pinfunction "GND_A1_B12") (pintype "power_in"))
      (node (ref "J4") (pin "SH1") (pinfunction "SHIELD_SH1") (pintype "passive"))
      (node (ref "J4") (pin "SH2") (pinfunction "SHIELD_SH2") (pintype "passive"))
      (node (ref "J4") (pin "SH3") (pinfunction "SHIELD_SH3") (pintype "passive"))
      (node (ref "J4") (pin "SH4") (pinfunction "SHIELD_SH4") (pintype "passive"))
      (node (ref "R1_USB") (pin "1") (pinfunction "1_1") (pintype "bidirectional"))
      (node (ref "R2_EP_DR") (pin "1") (pinfunction "1_1") (pintype "bidirectional"))
      (node (ref "R2_USB") (pin "2") (pinfunction "2_2") (pintype "bidirectional"))
      (node (ref "R3") (pin "1") (pinfunction "1_1") (pintype "bidirectional"))
      (node (ref "R9") (pin "1") (pinfunction "1_1") (pintype "bidirectional"))
      (node (ref "R_TYPE_SEL") (pin "1") (pinfunction "1_1") (pintype "bidirectional"))
      (node (ref "SJ1") (pin "1") (pinfunction "1_1") (pintype "passive"))
      (node (ref "SW_DN") (pin "1") (pinfunction "1_1") (pintype "passive"))
      (node (ref "SW_ENT") (pin "1") (pinfunction "1_1") (pintype "passive"))
      (node (ref "SW_UP") (pin "1") (pinfunction "1_1") (pintype "passive"))
      (node (ref "TP_BAT_GND") (pin "TP") (pinfunction "TP_TP") (pintype "input"))
      (node (ref "TP_GND") (pin "TP") (pinfunction "TP_TP") (pintype "input"))
      (node (ref "U1") (pin "P$74") (pinfunction "VSS_PAD_P$74") (pintype "bidirectional"))
      (node (ref "U1") (pin "P$75") (pinfunction "VSS_PAD_P$75") (pintype "bidirectional"))
      (node (ref "U1") (pin "P$76") (pinfunction "VSS_PAD_P$76") (pintype "bidirectional"))
      (node (ref "U1") (pin "P$77") (pinfunction "VSS_PAD_P$77") (pintype "bidirectional"))
      (node (ref "U1") (pin "P$78") (pinfunction "VSS_PAD_P$78") (pintype "bidirectional"))
      (node (ref "U1") (pin "P$79") (pinfunction "VSS_PAD_P$79") (pintype "bidirectional"))
      (node (ref "U1") (pin "P$80") (pinfunction "VSS_PAD_P$80") (pintype "bidirectional"))
      (node (ref "U1") (pin "P$81") (pinfunction "VSS_PAD_P$81") (pintype "bidirectional"))
      (node (ref "U1") (pin "P$82") (pinfunction "VSS_PAD_P$82") (pintype "bidirectional"))
      (node (ref "U1") (pin "P$83") (pinfunction "VSS_PAD_P$83") (pintype "bidirectional"))
      (node (ref "U1") (pin "P$84") (pinfunction "VSS_PAD_P$84") (pintype "bidirectional"))
      (node (ref "U1") (pin "P$85") (pinfunction "VSS_PAD_P$85") (pintype "bidirectional"))
      (node (ref "U1") (pin "P$86") (pinfunction "VSS_PAD_P$86") (pintype "bidirectional"))
      (node (ref "U1") (pin "P$87") (pinfunction "VSS_PAD_P$87") (pintype "bidirectional"))
      (node (ref "U1") (pin "P$88") (pinfunction "VSS_PAD_P$88") (pintype "bidirectional"))
      (node (ref "U1") (pin "P$89") (pinfunction "VSS_PAD_P$89") (pintype "bidirectional"))
      (node (ref "U1") (pin "P$90") (pinfunction "VSS_PAD_P$90") (pintype "bidirectional"))
      (node (ref "U1") (pin "P$B7") (pinfunction "VSS_P$B7") (pintype "power_in"))
      (node (ref "U1") (pin "P$F23") (pinfunction "VSS_PA_P$F23") (pintype "bidirectional"))
      (node (ref "U3") (pin "1") (pinfunction "CTG_1") (pintype "power_in"))
      (node (ref "U3") (pin "4") (pinfunction "GND_4") (pintype "power_in"))
      (node (ref "U3") (pin "6") (pinfunction "QSTRT_6") (pintype "input"))
      (node (ref "U3") (pin "9") (pinfunction "EP_9") (pintype "power_in"))
      (node (ref "X1") (pin "2") (pinfunction "2_2") (pintype "passive"))
      (node (ref "X1") (pin "4") (pinfunction "4_4") (pintype "passive"))
    )
    (net (code "16") (name "HAPTIC_EN") (class "Default")
      (node (ref "IC2") (pin "A1") (pinfunction "EN_A1") (pintype "bidirectional"))
      (node (ref "U1") (pin "P$U1") (pinfunction "P0.12_P$U1") (pintype "bidirectional"))
    )
    (net (code "17") (name "IMU_INT1") (class "Default")
      (node (ref "IC3") (pin "5") (pinfunction "INT1_5") (pintype "bidirectional"))
      (node (ref "U1") (pin "P$N1") (pinfunction "P0.08_P$N1") (pintype "bidirectional"))
    )
    (net (code "18") (name "IMU_INT2") (class "Default")
      (node (ref "IC3") (pin "6") (pinfunction "INT2_6") (pintype "bidirectional"))
      (node (ref "U1") (pin "P$P2") (pinfunction "P1.08_P$P2") (pintype "bidirectional"))
    )
    (net (code "19") (name "LX1") (class "Default")
      (node (ref "IC9") (pin "B2") (pinfunction "SW1_1_B2") (pintype "bidirectional"))
      (node (ref "IC9") (pin "B3") (pinfunction "SW1_2_B3") (pintype "bidirectional"))
      (node (ref "L7") (pin "1") (pinfunction "1_1") (pintype "bidirectional"))
    )
    (net (code "20") (name "LX2") (class "Default")
      (node (ref "IC9") (pin "D2") (pinfunction "SW2_1_D2") (pintype "bidirectional"))
      (node (ref "IC9") (pin "D3") (pinfunction "SW2_2_D3") (pintype "bidirectional"))
      (node (ref "L7") (pin "2") (pinfunction "2_2") (pintype "bidirectional"))
    )
    (net (code "21") (name "MOSI") (class "Default")
      (node (ref "J1") (pin "14") (pinfunction "14_14") (pintype "bidirectional"))
      (node (ref "U1") (pin "P$B13") (pinfunction "P0.03/AIN1_P$B13") (pintype "bidirectional"))
    )
    (net (code "22") (name "Net-(ANT1-FEED)") (class "Default")
      (node (ref "ANT1") (pin "1") (pinfunction "FEED_1") (pintype "input"))
      (node (ref "C22") (pin "1") (pinfunction "1_1") (pintype "passive"))
      (node (ref "C4") (pin "1") (pinfunction "1_1") (pintype "passive"))
      (node (ref "L1") (pin "2") (pinfunction "2_2") (pintype "passive"))
    )
    (net (code "23") (name "Net-(D2-K)") (class "Default")
      (node (ref "C2-EP-DR") (pin "1") (pinfunction "1_1") (pintype "passive"))
      (node (ref "D2") (pin "1") (pinfunction "K_1") (pintype "bidirectional"))
      (node (ref "D4") (pin "2") (pinfunction "A_2") (pintype "bidirectional"))
    )
    (net (code "24") (name "Net-(D5-A)") (class "Default")
      (node (ref "C2-EP-DR") (pin "2") (pinfunction "2_2") (pintype "passive"))
      (node (ref "D5") (pin "2") (pinfunction "A_2") (pintype "bidirectional"))
      (node (ref "L5") (pin "1") (pinfunction "1_1") (pintype "passive"))
      (node (ref "Q3") (pin "3") (pinfunction "D_3") (pintype "bidirectional"))
    )
    (net (code "25") (name "Net-(EPD_C1-Pad2)") (class "Default")
      (node (ref "EPD_C1") (pin "2") (pinfunction "2_2") (pintype "passive"))
      (node (ref "J1") (pin "5") (pinfunction "5_5") (pintype "bidirectional"))
    )
    (net (code "26") (name "Net-(EPD_C2-Pad2)") (class "Default")
      (node (ref "EPD_C2") (pin "2") (pinfunction "2_2") (pintype "passive"))
      (node (ref "J1") (pin "4") (pinfunction "4_4") (pintype "bidirectional"))
    )
    (net (code "27") (name "Net-(EPD_C6-Pad2)") (class "Default")
      (node (ref "EPD_C6") (pin "2") (pinfunction "2_2") (pintype "passive"))
      (node (ref "J1") (pin "18") (pinfunction "18_18") (pintype "bidirectional"))
    )
    (net (code "28") (name "Net-(EPD_C7-Pad2)") (class "Default")
      (node (ref "EPD_C7") (pin "2") (pinfunction "2_2") (pintype "passive"))
      (node (ref "J1") (pin "19") (pinfunction "19_19") (pintype "bidirectional"))
    )
    (net (code "29") (name "Net-(EPD_C8-Pad2)") (class "Default")
      (node (ref "EPD_C8") (pin "2") (pinfunction "2_2") (pintype "passive"))
      (node (ref "J1") (pin "20") (pinfunction "20_20") (pintype "bidirectional"))
    )
    (net (code "30") (name "Net-(EPD_C10-Pad2)") (class "Default")
      (node (ref "EPD_C10") (pin "2") (pinfunction "2_2") (pintype "passive"))
      (node (ref "J1") (pin "22") (pinfunction "22_22") (pintype "bidirectional"))
    )
    (net (code "31") (name "Net-(EPD_C12-Pad2)") (class "Default")
      (node (ref "EPD_C12") (pin "2") (pinfunction "2_2") (pintype "passive"))
      (node (ref "J1") (pin "24") (pinfunction "24_24") (pintype "bidirectional"))
    )
    (net (code "32") (name "Net-(IC1-TS{slash}MR)") (class "Default")
      (node (ref "IC1") (pin "D1") (pinfunction "TS/MR_D1") (pintype "bidirectional"))
      (node (ref "R9") (pin "2") (pinfunction "2_2") (pintype "bidirectional"))
    )
    (net (code "33") (name "Net-(IC2-REG)") (class "Default")
      (node (ref "C32") (pin "2") (pinfunction "2_2") (pintype "passive"))
      (node (ref "IC2") (pin "A2") (pinfunction "REG_A2") (pintype "bidirectional"))
    )
    (net (code "34") (name "Net-(IC3-SDO)") (class "Default")
      (node (ref "IC3") (pin "1") (pinfunction "SDO_1") (pintype "bidirectional"))
      (node (ref "R3") (pin "2") (pinfunction "2_2") (pintype "bidirectional"))
    )
    (net (code "35") (name "Net-(IC9-SCL)") (class "Default")
      (node (ref "IC9") (pin "D1") (pinfunction "SCL_D1") (pintype "bidirectional"))
      (node (ref "R4") (pin "2") (pinfunction "2_2") (pintype "bidirectional"))
    )
    (net (code "36") (name "Net-(IC9-SDA)") (class "Default")
      (node (ref "IC9") (pin "E1") (pinfunction "SDA_E1") (pintype "bidirectional"))
      (node (ref "R2") (pin "2") (pinfunction "2_2") (pintype "bidirectional"))
    )
    (net (code "37") (name "Net-(J4-CC1)") (class "Default")
      (node (ref "J4") (pin "A5") (pinfunction "CC1_A5") (pintype "bidirectional"))
      (node (ref "R1_USB") (pin "2") (pinfunction "2_2") (pintype "bidirectional"))
    )
    (net (code "38") (name "Net-(J4-CC2)") (class "Default")
      (node (ref "J4") (pin "B5") (pinfunction "CC2_B5") (pintype "bidirectional"))
      (node (ref "R2_USB") (pin "1") (pinfunction "1_1") (pintype "bidirectional"))
    )
    (net (code "39") (name "Net-(L2-Pad2)") (class "Default")
      (node (ref "L2") (pin "2") (pinfunction "2_2") (pintype "passive"))
      (node (ref "L3") (pin "1") (pinfunction "1_1") (pintype "passive"))
    )
    (net (code "40") (name "Net-(R1_EP_DR-Pad1)") (class "Default")
      (node (ref "R1_EP_DR") (pin "1") (pinfunction "1_1") (pintype "bidirectional"))
      (node (ref "R_TYPE_SEL") (pin "2") (pinfunction "2_2") (pintype "bidirectional"))
      (node (ref "SJ1") (pin "2") (pinfunction "2_2") (pintype "passive"))
    )
    (net (code "41") (name "Net-(U1-ANT)") (class "Default")
      (node (ref "C3") (pin "1") (pinfunction "1_1") (pintype "passive"))
      (node (ref "L1") (pin "1") (pinfunction "1_1") (pintype "passive"))
      (node (ref "U1") (pin "P$H23") (pinfunction "ANT_P$H23") (pintype "bidirectional"))
    )
    (net (code "42") (name "Net-(U1-DCC)") (class "Default")
      (node (ref "L2") (pin "1") (pinfunction "1_1") (pintype "passive"))
      (node (ref "U1") (pin "P$B3") (pinfunction "DCC_P$B3") (pintype "output"))
    )
    (net (code "43") (name "Net-(U1-DEC1)") (class "Default")
      (node (ref "C5") (pin "1") (pinfunction "1_1") (pintype "passive"))
      (node (ref "U1") (pin "P$C1") (pinfunction "DEC1_P$C1") (pintype "power_in"))
    )
    (net (code "44") (name "Net-(U1-DEC2)") (class "Default")
      (node (ref "C13") (pin "1") (pinfunction "1_1") (pintype "passive"))
      (node (ref "U1") (pin "P$A18") (pinfunction "DEC2_P$A18") (pintype "bidirectional"))
    )
    (net (code "45") (name "Net-(U1-DEC3V3)") (class "Default")
      (node (ref "C20") (pin "1") (pinfunction "1_1") (pintype "passive"))
      (node (ref "U1") (pin "P$AC5") (pinfunction "DEC3V3_P$AC5") (pintype "bidirectional"))
    )
    (net (code "46") (name "Net-(U1-DEC5)") (class "Default")
      (node (ref "C9") (pin "1") (pinfunction "1_1") (pintype "passive"))
      (node (ref "U1") (pin "P$N24") (pinfunction "DEC5_P$N24") (pintype "bidirectional"))
    )
    (net (code "47") (name "Net-(U1-XC1)") (class "Default")
      (node (ref "C1") (pin "1") (pinfunction "1_1") (pintype "passive"))
      (node (ref "U1") (pin "P$B24") (pinfunction "XC1_P$B24") (pintype "input"))
      (node (ref "X1") (pin "1") (pinfunction "1_1") (pintype "passive"))
    )
    (net (code "48") (name "Net-(U1-XC2)") (class "Default")
      (node (ref "C2") (pin "1") (pinfunction "1_1") (pintype "passive"))
      (node (ref "U1") (pin "P$A23") (pinfunction "XC2_P$A23") (pintype "output"))
      (node (ref "X1") (pin "3") (pinfunction "3_3") (pintype "passive"))
    )
    (net (code "49") (name "OUT+") (class "Default")
      (node (ref "IC2") (pin "A3") (pinfunction "OUT+_A3") (pintype "bidirectional"))
      (node (ref "TP_OP") (pin "TP") (pinfunction "TP_TP") (pintype "input"))
    )
    (net (code "50") (name "OUT-") (class "Default")
      (node (ref "IC2") (pin "C3") (pinfunction "OUT-_C3") (pintype "bidirectional"))
      (node (ref "TP_ON") (pin "TP") (pinfunction "TP_TP") (pintype "input"))
    )
    (net (code "51") (name "P0.00") (class "Default")
      (node (ref "C17") (pin "2") (pinfunction "2_2") (pintype "passive"))
      (node (ref "U1") (pin "P$D2") (pinfunction "P0.00/XL1_P$D2") (pintype "bidirectional"))
      (node (ref "X2") (pin "1") (pinfunction "1_1") (pintype "passive"))
    )
    (net (code "52") (name "P0.01") (class "Default")
      (node (ref "C18") (pin "2") (pinfunction "2_2") (pintype "passive"))
      (node (ref "U1") (pin "P$F2") (pinfunction "P0.01/XL2_P$F2") (pintype "bidirectional"))
      (node (ref "X2") (pin "2") (pinfunction "2_2") (pintype "passive"))
    )
    (net (code "53") (name "P0.04") (class "Default")
      (node (ref "U1") (pin "P$J1") (pinfunction "P0.04/AIN2_P$J1") (pintype "bidirectional"))
    )
    (net (code "54") (name "P0.09") (class "Default")
      (node (ref "U1") (pin "P$L24") (pinfunction "P0.09/NFC1_P$L24") (pintype "bidirectional"))
    )
    (net (code "55") (name "P0.13") (class "Default")
      (node (ref "C30") (pin "2") (pinfunction "2_2") (pintype "passive"))
      (node (ref "R5") (pin "1") (pinfunction "1_1") (pintype "bidirectional"))
      (node (ref "SW_UP") (pin "2") (pinfunction "2_2") (pintype "passive"))
      (node (ref "U1") (pin "P$AD8") (pinfunction "P0.13_P$AD8") (pintype "bidirectional"))
    )
    (net (code "56") (name "P0.14") (class "Default")
      (node (ref "C31") (pin "2") (pinfunction "2_2") (pintype "passive"))
      (node (ref "R8") (pin "1") (pinfunction "1_1") (pintype "bidirectional"))
      (node (ref "SW_ENT") (pin "2") (pinfunction "2_2") (pintype "passive"))
      (node (ref "U1") (pin "P$AC9") (pinfunction "P0.14_P$AC9") (pintype "bidirectional"))
    )
    (net (code "57") (name "P0.19") (class "Default")
      (node (ref "U1") (pin "P$AC15") (pinfunction "P0.19_P$AC15") (pintype "bidirectional"))
    )
    (net (code "58") (name "P0.20") (class "Default")
      (node (ref "U1") (pin "P$AD16") (pinfunction "P0.20_P$AD16") (pintype "bidirectional"))
    )
    (net (code "59") (name "P0.21") (class "Default")
      (node (ref "U1") (pin "P$AC17") (pinfunction "P0.21_P$AC17") (pintype "bidirectional"))
    )
    (net (code "60") (name "P0.22") (class "Default")
      (node (ref "U1") (pin "P$AD18") (pinfunction "P0.22_P$AD18") (pintype "bidirectional"))
    )
    (net (code "61") (name "P0.23") (class "Default")
      (node (ref "U1") (pin "P$AC19") (pinfunction "P0.23_P$AC19") (pintype "bidirectional"))
    )
    (net (code "62") (name "P0.24") (class "Default")
      (node (ref "U1") (pin "P$AD20") (pinfunction "P0.24_P$AD20") (pintype "bidirectional"))
    )
    (net (code "63") (name "P0.25") (class "Default")
      (node (ref "U1") (pin "P$AC21") (pinfunction "P0.25_P$AC21") (pintype "bidirectional"))
    )
    (net (code "64") (name "P0.26") (class "Default")
      (node (ref "U1") (pin "P$G1") (pinfunction "P0.26_P$G1") (pintype "bidirectional"))
    )
    (net (code "65") (name "P0.27") (class "Default")
      (node (ref "U1") (pin "P$H2") (pinfunction "P0.27_P$H2") (pintype "bidirectional"))
    )
    (net (code "66") (name "P0.28") (class "Default")
      (node (ref "U1") (pin "P$B11") (pinfunction "P0.28/AIN4_P$B11") (pintype "bidirectional"))
    )
    (net (code "67") (name "P0.29") (class "Default")
      (node (ref "U1") (pin "P$A10") (pinfunction "P0.29/AIN5_P$A10") (pintype "bidirectional"))
    )
    (net (code "68") (name "P0.30") (class "Default")
      (node (ref "U1") (pin "P$B9") (pinfunction "P0.30/AIN6_P$B9") (pintype "bidirectional"))
    )
    (net (code "69") (name "P0.31") (class "Default")
      (node (ref "U1") (pin "P$A8") (pinfunction "P0.31/AIN7_P$A8") (pintype "bidirectional"))
    )
    (net (code "70") (name "P1.01") (class "Default")
      (node (ref "Q1") (pin "1") (pinfunction "G_1") (pintype "bidirectional"))
      (node (ref "R_PWR_EPD") (pin "1") (pinfunction "1_1") (pintype "bidirectional"))
      (node (ref "U1") (pin "P$Y23") (pinfunction "P1.01_P$Y23") (pintype "bidirectional"))
    )
    (net (code "71") (name "P1.02") (class "Default")
      (node (ref "C29") (pin "2") (pinfunction "2_2") (pintype "passive"))
      (node (ref "R7") (pin "1") (pinfunction "1_1") (pintype "bidirectional"))
      (node (ref "SW_DN") (pin "2") (pinfunction "2_2") (pintype "passive"))
      (node (ref "U1") (pin "P$W24") (pinfunction "P1.02_P$W24") (pintype "bidirectional"))
    )
    (net (code "72") (name "P1.03") (class "Default")
      (node (ref "U1") (pin "P$V23") (pinfunction "P1.03_P$V23") (pintype "bidirectional"))
    )
    (net (code "73") (name "P1.04") (class "Default")
      (node (ref "U1") (pin "P$U24") (pinfunction "P1.04_P$U24") (pintype "bidirectional"))
    )
    (net (code "74") (name "P1.05") (class "Default")
      (node (ref "U1") (pin "P$T23") (pinfunction "P1.05_P$T23") (pintype "bidirectional"))
    )
    (net (code "75") (name "P1.06") (class "Default")
      (node (ref "U1") (pin "P$R24") (pinfunction "P1.06_P$R24") (pintype "bidirectional"))
    )
    (net (code "76") (name "P1.07") (class "Default")
      (node (ref "U1") (pin "P$P23") (pinfunction "P1.07_P$P23") (pintype "bidirectional"))
    )
    (net (code "77") (name "P1.09") (class "Default")
      (node (ref "U1") (pin "P$R1") (pinfunction "P1.09_P$R1") (pintype "bidirectional"))
    )
    (net (code "78") (name "P1.10") (class "Default")
      (node (ref "U1") (pin "P$A20") (pinfunction "P1.10_P$A20") (pintype "bidirectional"))
    )
    (net (code "79") (name "P1.11") (class "Default")
      (node (ref "U1") (pin "P$B19") (pinfunction "P1.11_P$B19") (pintype "bidirectional"))
    )
    (net (code "80") (name "P1.12") (class "Default")
      (node (ref "U1") (pin "P$B17") (pinfunction "P1.12_P$B17") (pintype "bidirectional"))
    )
    (net (code "81") (name "P1.13") (class "Default")
      (node (ref "U1") (pin "P$A16") (pinfunction "P1.13_P$A16") (pintype "bidirectional"))
    )
    (net (code "82") (name "P1.14") (class "Default")
      (node (ref "U1") (pin "P$B15") (pinfunction "P1.14_P$B15") (pintype "bidirectional"))
    )
    (net (code "83") (name "P1.15") (class "Default")
      (node (ref "U1") (pin "P$A14") (pinfunction "P1.15_P$A14") (pintype "bidirectional"))
    )
    (net (code "84") (name "PMIC_INT") (class "Default")
      (node (ref "IC1") (pin "A1") (pinfunction "~{INT}_A1") (pintype "bidirectional"))
      (node (ref "U1") (pin "P$T2") (pinfunction "P0.11_P$T2") (pintype "bidirectional"))
    )
    (net (code "85") (name "PREVGH") (class "Default")
      (node (ref "D5") (pin "1") (pinfunction "K_1") (pintype "bidirectional"))
      (node (ref "EPD_C9") (pin "2") (pinfunction "2_2") (pintype "passive"))
      (node (ref "J1") (pin "21") (pinfunction "21_21") (pintype "bidirectional"))
    )
    (net (code "86") (name "PREVGL") (class "Default")
      (node (ref "D2") (pin "2") (pinfunction "A_2") (pintype "bidirectional"))
      (node (ref "EPD_C11") (pin "2") (pinfunction "2_2") (pintype "passive"))
      (node (ref "J1") (pin "23") (pinfunction "23_23") (pintype "bidirectional"))
    )
    (net (code "87") (name "RESE") (class "Default")
      (node (ref "J1") (pin "3") (pinfunction "3_3") (pintype "bidirectional"))
      (node (ref "Q3") (pin "2") (pinfunction "S_2") (pintype "bidirectional"))
      (node (ref "R1_EP_DR") (pin "2") (pinfunction "2_2") (pintype "bidirectional"))
    )
    (net (code "88") (name "RESET") (class "Default")
      (node (ref "J2") (pin "6") (pinfunction "6_6") (pintype "bidirectional"))
      (node (ref "TP_RESET") (pin "TP") (pinfunction "TP_TP") (pintype "input"))
      (node (ref "U1") (pin "P$AC13") (pinfunction "P0.18/RESET_P$AC13") (pintype "bidirectional"))
    )
    (net (code "89") (name "SCK") (class "Default")
      (node (ref "J1") (pin "13") (pinfunction "13_13") (pintype "bidirectional"))
      (node (ref "U1") (pin "P$A12") (pinfunction "P0.02/AIN0_P$A12") (pintype "bidirectional"))
    )
    (net (code "90") (name "SCL") (class "Default")
      (node (ref "IC1") (pin "B1") (pinfunction "SCL_B1") (pintype "bidirectional"))
      (node (ref "IC2") (pin "C1") (pinfunction "SCL_C1") (pintype "bidirectional"))
      (node (ref "IC3") (pin "12") (pinfunction "SCX_12") (pintype "bidirectional"))
      (node (ref "R17") (pin "2") (pinfunction "2_2") (pintype "bidirectional"))
      (node (ref "R4") (pin "1") (pinfunction "1_1") (pintype "bidirectional"))
      (node (ref "TP_SCL") (pin "TP") (pinfunction "TP_TP") (pintype "input"))
      (node (ref "U1") (pin "P$M2") (pinfunction "P0.07_P$M2") (pintype "bidirectional"))
      (node (ref "U3") (pin "7") (pinfunction "SCL_7") (pintype "input"))
    )
    (net (code "91") (name "SDA") (class "Default")
      (node (ref "IC1") (pin "C1") (pinfunction "SDA_C1") (pintype "bidirectional"))
      (node (ref "IC2") (pin "B2") (pinfunction "SDA_B2") (pintype "bidirectional"))
      (node (ref "IC3") (pin "2") (pinfunction "SDX_2") (pintype "bidirectional"))
      (node (ref "R18") (pin "2") (pinfunction "2_2") (pintype "bidirectional"))
      (node (ref "R2") (pin "1") (pinfunction "1_1") (pintype "bidirectional"))
      (node (ref "TP_SDA") (pin "TP") (pinfunction "TP_TP") (pintype "input"))
      (node (ref "U1") (pin "P$L1") (pinfunction "P0.06_P$L1") (pintype "bidirectional"))
      (node (ref "U3") (pin "8") (pinfunction "SDA_8") (pintype "bidirectional"))
    )
    (net (code "92") (name "SWDCLK") (class "Default")
      (node (ref "J2") (pin "4") (pinfunction "4_4") (pintype "bidirectional"))
      (node (ref "TP_SWDCLK") (pin "TP") (pinfunction "TP_TP") (pintype "input"))
      (node (ref "U1") (pin "P$AA24") (pinfunction "SWDCLK_P$AA24") (pintype "input"))
    )
    (net (code "93") (name "SWDIO") (class "Default")
      (node (ref "J2") (pin "2") (pinfunction "2_2") (pintype "bidirectional"))
      (node (ref "TP_SWDIO") (pin "TP") (pinfunction "TP_TP") (pintype "input"))
      (node (ref "U1") (pin "P$AC24") (pinfunction "SWDIO_P$AC24") (pintype "bidirectional"))
    )
    (net (code "94") (name "SWO") (class "Default")
      (node (ref "TP_SWO") (pin "TP") (pinfunction "TP_TP") (pintype "input"))
      (node (ref "U1") (pin "P$AD22") (pinfunction "P1.00_P$AD22") (pintype "bidirectional"))
    )
    (net (code "95") (name "VBAT") (class "Default")
      (node (ref "C27") (pin "2") (pinfunction "2_2") (pintype "passive"))
      (node (ref "C37") (pin "2") (pinfunction "2_2") (pintype "passive"))
      (node (ref "IC1") (pin "C2") (pinfunction "BAT_C2") (pintype "bidirectional"))
      (node (ref "TP_VBAT") (pin "TP") (pinfunction "TP_TP") (pintype "input"))
      (node (ref "U3") (pin "2") (pinfunction "CELL_2") (pintype "power_in"))
      (node (ref "U3") (pin "3") (pinfunction "VDD_3") (pintype "power_in"))
    )
    (net (code "96") (name "VBUS") (class "Default")
      (node (ref "C21") (pin "1") (pinfunction "1_1") (pintype "passive"))
      (node (ref "C38") (pin "2") (pinfunction "2_2") (pintype "passive"))
      (node (ref "C42") (pin "2") (pinfunction "2_2") (pintype "passive"))
      (node (ref "C43") (pin "1") (pinfunction "1_1") (pintype "passive"))
      (node (ref "D3") (pin "5") (pinfunction "VBUS_5") (pintype "bidirectional"))
      (node (ref "IC1") (pin "A2") (pinfunction "IN_A2") (pintype "bidirectional"))
      (node (ref "J4") (pin "A4_B9") (pinfunction "VBUS_A4_B9") (pintype "power_in"))
      (node (ref "J4") (pin "A9_B4") (pinfunction "VBUS_A9_B4") (pintype "power_in"))
      (node (ref "U1") (pin "P$AD2") (pinfunction "VBUS_P$AD2") (pintype "power_in"))
    )
    (net (code "97") (name "VREG") (class "Default")
      (node (ref "C23") (pin "2") (pinfunction "2_2") (pintype "passive"))
      (node (ref "C24") (pin "2") (pinfunction "2_2") (pintype "passive"))
      (node (ref "C39") (pin "1") (pinfunction "1_1") (pintype "passive"))
      (node (ref "IC1") (pin "B2") (pinfunction "SYS_B2") (pintype "bidirectional"))
      (node (ref "IC9") (pin "A1") (pinfunction "EN_A1") (pintype "bidirectional"))
      (node (ref "IC9") (pin "A2") (pinfunction "VIN_1_A2") (pintype "bidirectional"))
      (node (ref "IC9") (pin "A3") (pinfunction "VIN_2_A3") (pintype "bidirectional"))
      (node (ref "TP_VREG") (pin "TP") (pinfunction "TP_TP") (pintype "input"))
    )
    (net (code "98") (name "unconnected-(ANT1-NC-Pad2)") (class "Default")
      (node (ref "ANT1") (pin "2") (pinfunction "NC_2") (pintype "no_connect"))
    )
    (net (code "99") (name "unconnected-(IC3-ASCL-Pad11)") (class "Default")
      (node (ref "IC3") (pin "11") (pinfunction "ASCL_11") (pintype "bidirectional"))
    )
    (net (code "100") (name "unconnected-(IC3-ASDA-Pad4)") (class "Default")
      (node (ref "IC3") (pin "4") (pinfunction "ASDA_4") (pintype "bidirectional"))
    )
    (net (code "101") (name "unconnected-(J1-Pad1)") (class "Default")
      (node (ref "J1") (pin "1") (pinfunction "1_1") (pintype "bidirectional"))
    )
    (net (code "102") (name "unconnected-(J1-Pad6)") (class "Default")
      (node (ref "J1") (pin "6") (pinfunction "6_6") (pintype "bidirectional"))
    )
    (net (code "103") (name "unconnected-(J1-Pad7)") (class "Default")
      (node (ref "J1") (pin "7") (pinfunction "7_7") (pintype "bidirectional"))
    )
    (net (code "104") (name "unconnected-(J4-SBU1-PadA8)") (class "Default")
      (node (ref "J4") (pin "A8") (pinfunction "SBU1_A8") (pintype "bidirectional"))
    )
    (net (code "105") (name "unconnected-(J4-SBU2-PadB8)") (class "Default")
      (node (ref "J4") (pin "B8") (pinfunction "SBU2_B8") (pintype "bidirectional"))
    )
    (net (code "106") (name "unconnected-(U1-DCCH-PadP$AB2)") (class "Default")
      (node (ref "U1") (pin "P$AB2") (pinfunction "DCCH_P$AB2") (pintype "bidirectional"))
    )
  )
)
